# board.net
KiCad netlist of a schematic drawn in EAGLE
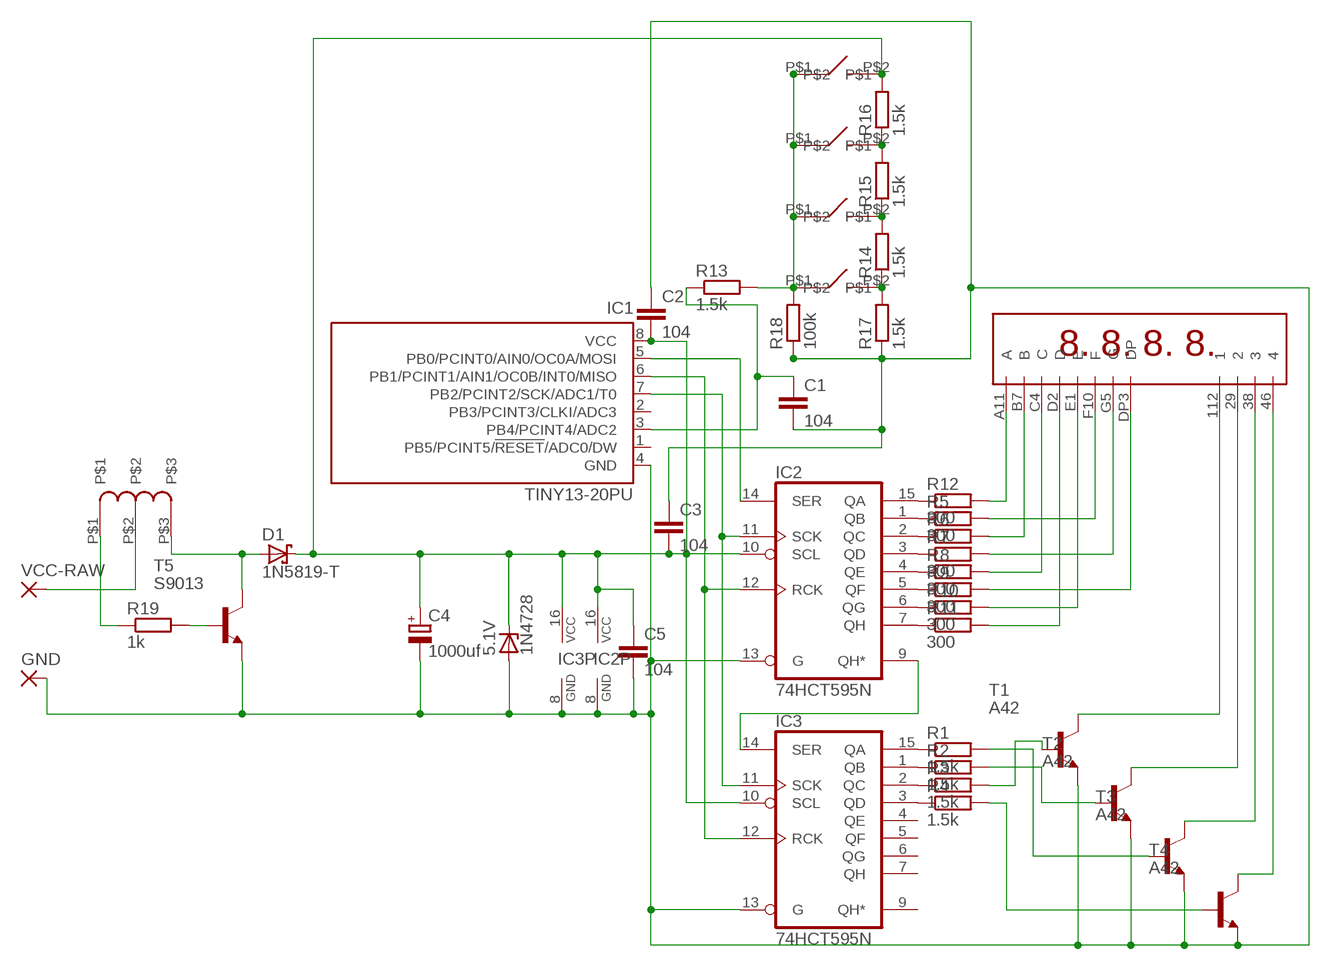
[diagram p0: schematic, sheet 1]

(export (version "E")
  (design (tool "Eeschema 10.0.6"))
  (components
    (comp (ref "5.1V")
      (value "1N4728")
      (footprint "eagle-import:DO41Z10")
      (libsource (lib "eagle-import") (part "1N4728"))
    )
    (comp (ref "BTN1")
      (value "BTN-6X6")
      (footprint "eagle-import:BTN-6X6")
      (libsource (lib "eagle-import") (part "BTN-6X6"))
    )
    (comp (ref "BTN2")
      (value "BTN-6X6")
      (footprint "eagle-import:BTN-6X6")
      (libsource (lib "eagle-import") (part "BTN-6X6"))
    )
    (comp (ref "BTN3")
      (value "BTN-6X6")
      (footprint "eagle-import:BTN-6X6")
      (libsource (lib "eagle-import") (part "BTN-6X6"))
    )
    (comp (ref "BTN4")
      (value "BTN-6X6")
      (footprint "eagle-import:BTN-6X6")
      (libsource (lib "eagle-import") (part "BTN-6X6"))
    )
    (comp (ref "C1")
      (value "104")
      (footprint "eagle-import:C050-025X075")
      (libsource (lib "eagle-import") (part "C-EU050-025X075"))
    )
    (comp (ref "C2")
      (value "104")
      (footprint "eagle-import:C050-025X075")
      (libsource (lib "eagle-import") (part "C-EU050-025X075"))
    )
    (comp (ref "C3")
      (value "104")
      (footprint "eagle-import:C050-025X075")
      (libsource (lib "eagle-import") (part "C-EU050-025X075"))
    )
    (comp (ref "C4")
      (value "1000uf")
      (footprint "eagle-import:E3,5-8")
      (libsource (lib "eagle-import") (part "CPOL-EUE3.5-8"))
    )
    (comp (ref "C5")
      (value "104")
      (footprint "eagle-import:C050-025X075")
      (libsource (lib "eagle-import") (part "C-EU050-025X075"))
    )
    (comp (ref "D1")
      (value "1N5819-T")
      (footprint "eagle-import:DO41-7.6")
      (libsource (lib "eagle-import") (part "1N5819-T"))
    )
    (comp (ref "GND")
      (value "2,54/0,8")
      (footprint "eagle-import:2,54_0,8")
      (libsource (lib "eagle-import") (part "2,54/0,8"))
    )
    (comp (ref "IC1")
      (value "TINY13-20PU")
      (footprint "eagle-import:DIL08")
      (fields (field (name "MPN") "ATTINY13-20PU"))
      (libsource (lib "eagle-import") (part "TINY13PU-20"))
    )
    (comp (ref "IC2")
      (value "74HCT595N")
      (footprint "eagle-import:DIL16")
      (libsource (lib "eagle-import") (part "74595NHCT"))
    )
    (comp (ref "IC3")
      (value "74HCT595N")
      (footprint "eagle-import:DIL16")
      (libsource (lib "eagle-import") (part "74595NHCT"))
    )
    (comp (ref "R1")
      (value "1.5k")
      (footprint "eagle-import:0207_2V")
      (libsource (lib "eagle-import") (part "resistor_348_R-EU_0207/2V"))
    )
    (comp (ref "R2")
      (value "1.5k")
      (footprint "eagle-import:0207_2V")
      (libsource (lib "eagle-import") (part "resistor_348_R-EU_0207/2V"))
    )
    (comp (ref "R3")
      (value "1.5k")
      (footprint "eagle-import:0207_2V")
      (libsource (lib "eagle-import") (part "resistor_348_R-EU_0207/2V"))
    )
    (comp (ref "R4")
      (value "1.5k")
      (footprint "eagle-import:0207_2V")
      (libsource (lib "eagle-import") (part "resistor_348_R-EU_0207/2V"))
    )
    (comp (ref "R5")
      (value "300")
      (footprint "eagle-import:0207_2V")
      (libsource (lib "eagle-import") (part "resistor_348_R-EU_0207/2V"))
    )
    (comp (ref "R6")
      (value "R-EU_0207/2V")
      (footprint "eagle-import:0207_2V")
      (libsource (lib "eagle-import") (part "resistor_348_R-EU_0207/2V"))
    )
    (comp (ref "R7")
      (value "300")
      (footprint "eagle-import:0207_2V")
      (libsource (lib "eagle-import") (part "resistor_348_R-EU_0207/2V"))
    )
    (comp (ref "R8")
      (value "300")
      (footprint "eagle-import:0207_2V")
      (libsource (lib "eagle-import") (part "resistor_348_R-EU_0207/2V"))
    )
    (comp (ref "R9")
      (value "300")
      (footprint "eagle-import:0207_2V")
      (libsource (lib "eagle-import") (part "resistor_348_R-EU_0207/2V"))
    )
    (comp (ref "R10")
      (value "300")
      (footprint "eagle-import:0207_2V")
      (libsource (lib "eagle-import") (part "resistor_348_R-EU_0207/2V"))
    )
    (comp (ref "R11")
      (value "300")
      (footprint "eagle-import:0207_2V")
      (libsource (lib "eagle-import") (part "resistor_348_R-EU_0207/2V"))
    )
    (comp (ref "R12")
      (value "300")
      (footprint "eagle-import:0207_2V")
      (libsource (lib "eagle-import") (part "resistor_348_R-EU_0207/2V"))
    )
    (comp (ref "R13")
      (value "1.5k")
      (footprint "eagle-import:0204_7")
      (libsource (lib "eagle-import") (part "resistor_348_R-EU_0204/7"))
    )
    (comp (ref "R14")
      (value "1.5k")
      (footprint "eagle-import:0204_7")
      (libsource (lib "eagle-import") (part "R-EU_0204/7"))
    )
    (comp (ref "R15")
      (value "1.5k")
      (footprint "eagle-import:0204_7")
      (libsource (lib "eagle-import") (part "R-EU_0204/7"))
    )
    (comp (ref "R16")
      (value "1.5k")
      (footprint "eagle-import:0204_7")
      (libsource (lib "eagle-import") (part "R-EU_0204/7"))
    )
    (comp (ref "R17")
      (value "1.5k")
      (footprint "eagle-import:0204_7")
      (libsource (lib "eagle-import") (part "R-EU_0204/7"))
    )
    (comp (ref "R18")
      (value "100k")
      (footprint "eagle-import:0204_7")
      (libsource (lib "eagle-import") (part "resistor_348_R-EU_0204/7"))
    )
    (comp (ref "R19")
      (value "1k")
      (footprint "eagle-import:0207_2V")
      (libsource (lib "eagle-import") (part "resistor_348_R-EU_0207/2V"))
    )
    (comp (ref "T1")
      (value "A42")
      (footprint "eagle-import:TO92-EBC")
      (libsource (lib "eagle-import") (part "-NPN-TO92-EBCMPSA42"))
    )
    (comp (ref "T2")
      (value "A42")
      (footprint "eagle-import:TO92-EBC")
      (libsource (lib "eagle-import") (part "-NPN-TO92-EBCMPSA42"))
    )
    (comp (ref "T3")
      (value "A42")
      (footprint "eagle-import:TO92-EBC")
      (libsource (lib "eagle-import") (part "-NPN-TO92-EBCMPSA42"))
    )
    (comp (ref "T4")
      (value "A42")
      (footprint "eagle-import:TO92-EBC")
      (libsource (lib "eagle-import") (part "-NPN-TO92-EBCMPSA42"))
    )
    (comp (ref "T5")
      (value "S9013")
      (footprint "eagle-import:TO92-EBC")
      (libsource (lib "eagle-import") (part "-NPN-TO92-EBCMPSA42"))
    )
    (comp (ref "U$1")
      (value "KL-5641-ASR")
      (footprint "eagle-import:KL-5641-ASR")
      (libsource (lib "eagle-import") (part "KL-5641-ASR"))
    )
    (comp (ref "U$3")
      (value "TRANS")
      (footprint "eagle-import:TRANS")
      (libsource (lib "eagle-import") (part "TRANS"))
    )
    (comp (ref "VCC-RAW")
      (value "2,54/0,8")
      (footprint "eagle-import:2,54_0,8")
      (libsource (lib "eagle-import") (part "2,54/0,8"))
    )
  )
  (nets
    (net (code "1") (name "Net-(BTN1-PadP$1)") (class "Default")
      (node (ref "BTN1") (pin "P$1") (pinfunction "P$1_P$1") (pintype "bidirectional"))
      (node (ref "BTN2") (pin "P$1") (pinfunction "P$1_P$1") (pintype "bidirectional"))
      (node (ref "BTN3") (pin "P$1") (pinfunction "P$1_P$1") (pintype "bidirectional"))
      (node (ref "BTN4") (pin "P$1") (pinfunction "P$1_P$1") (pintype "bidirectional"))
      (node (ref "R13") (pin "2") (pinfunction "2_2") (pintype "passive"))
      (node (ref "R18") (pin "2") (pinfunction "2_2") (pintype "passive"))
    )
    (net (code "2") (name "Net-(BTN2-PadP$2)") (class "Default")
      (node (ref "BTN2") (pin "P$2") (pinfunction "P$2_P$2") (pintype "bidirectional"))
      (node (ref "R15") (pin "2") (pinfunction "2_2") (pintype "passive"))
      (node (ref "R16") (pin "1") (pinfunction "1_1") (pintype "passive"))
    )
    (net (code "3") (name "Net-(BTN3-PadP$2)") (class "Default")
      (node (ref "BTN3") (pin "P$2") (pinfunction "P$2_P$2") (pintype "bidirectional"))
      (node (ref "R14") (pin "2") (pinfunction "2_2") (pintype "passive"))
      (node (ref "R15") (pin "1") (pinfunction "1_1") (pintype "passive"))
    )
    (net (code "4") (name "Net-(BTN4-PadP$2)") (class "Default")
      (node (ref "BTN4") (pin "P$2") (pinfunction "P$2_P$2") (pintype "bidirectional"))
      (node (ref "R14") (pin "1") (pinfunction "1_1") (pintype "passive"))
      (node (ref "R17") (pin "2") (pinfunction "2_2") (pintype "passive"))
    )
    (net (code "5") (name "Net-(D1-PadA)") (class "Default")
      (node (ref "D1") (pin "A") (pinfunction "A_A") (pintype "passive"))
      (node (ref "T5") (pin "C") (pinfunction "C_C") (pintype "passive"))
      (node (ref "U$3") (pin "P$3") (pinfunction "P$3_P$3") (pintype "bidirectional"))
    )
    (net (code "6") (name "Net-(GND-P)") (class "Default")
      (node (ref "5.1V") (pin "A") (pinfunction "A_A") (pintype "passive"))
      (node (ref "C1") (pin "2") (pinfunction "2_2") (pintype "passive"))
      (node (ref "C2") (pin "1") (pinfunction "1_1") (pintype "passive"))
      (node (ref "C3") (pin "1") (pinfunction "1_1") (pintype "passive"))
      (node (ref "C4") (pin "-") (pinfunction "-_-") (pintype "passive"))
      (node (ref "C5") (pin "2") (pinfunction "2_2") (pintype "passive"))
      (node (ref "GND") (pin "1") (pinfunction "P_1") (pintype "passive"))
      (node (ref "IC1") (pin "4") (pinfunction "GND_4") (pintype "power_in"))
      (node (ref "IC2") (pin "13") (pinfunction "G_13") (pintype "input"))
      (node (ref "IC2") (pin "8") (pinfunction "GND_8") (pintype "power_in"))
      (node (ref "IC3") (pin "13") (pinfunction "G_13") (pintype "input"))
      (node (ref "IC3") (pin "8") (pinfunction "GND_8") (pintype "power_in"))
      (node (ref "R17") (pin "1") (pinfunction "1_1") (pintype "passive"))
      (node (ref "R18") (pin "1") (pinfunction "1_1") (pintype "passive"))
      (node (ref "T1") (pin "E") (pinfunction "E_E") (pintype "passive"))
      (node (ref "T2") (pin "E") (pinfunction "E_E") (pintype "passive"))
      (node (ref "T3") (pin "E") (pinfunction "E_E") (pintype "passive"))
      (node (ref "T4") (pin "E") (pinfunction "E_E") (pintype "passive"))
      (node (ref "T5") (pin "E") (pinfunction "E_E") (pintype "passive"))
    )
    (net (code "7") (name "Net-(IC1-PB0{slash}PCINT0{slash}AIN0{slash}OC0A{slash}MOSI)") (class "Default")
      (node (ref "IC1") (pin "5") (pinfunction "PB0/PCINT0/AIN0/OC0A/MOSI_5") (pintype "bidirectional"))
      (node (ref "IC2") (pin "14") (pinfunction "SER_14") (pintype "input"))
    )
    (net (code "8") (name "Net-(IC1-PB1{slash}PCINT1{slash}AIN1{slash}OC0B{slash}INT0{slash}MISO)") (class "Default")
      (node (ref "IC1") (pin "6") (pinfunction "PB1/PCINT1/AIN1/OC0B/INT0/MISO_6") (pintype "bidirectional"))
      (node (ref "IC2") (pin "12") (pinfunction "RCK_12") (pintype "input"))
      (node (ref "IC3") (pin "12") (pinfunction "RCK_12") (pintype "input"))
    )
    (net (code "9") (name "Net-(IC1-PB2{slash}PCINT2{slash}SCK{slash}ADC1{slash}T0)") (class "Default")
      (node (ref "IC1") (pin "7") (pinfunction "PB2/PCINT2/SCK/ADC1/T0_7") (pintype "bidirectional"))
      (node (ref "IC2") (pin "11") (pinfunction "SCK_11") (pintype "input"))
      (node (ref "IC3") (pin "11") (pinfunction "SCK_11") (pintype "input"))
    )
    (net (code "10") (name "Net-(IC1-PB4{slash}PCINT4{slash}ADC2)") (class "Default")
      (node (ref "C1") (pin "1") (pinfunction "1_1") (pintype "passive"))
      (node (ref "IC1") (pin "3") (pinfunction "PB4/PCINT4/ADC2_3") (pintype "bidirectional"))
      (node (ref "R13") (pin "1") (pinfunction "1_1") (pintype "passive"))
    )
    (net (code "11") (name "Net-(IC1-VCC)") (class "Default")
      (node (ref "5.1V") (pin "C") (pinfunction "C_C") (pintype "passive"))
      (node (ref "BTN1") (pin "P$2") (pinfunction "P$2_P$2") (pintype "bidirectional"))
      (node (ref "C2") (pin "2") (pinfunction "2_2") (pintype "passive"))
      (node (ref "C3") (pin "2") (pinfunction "2_2") (pintype "passive"))
      (node (ref "C4") (pin "+") (pinfunction "+_+") (pintype "passive"))
      (node (ref "C5") (pin "1") (pinfunction "1_1") (pintype "passive"))
      (node (ref "D1") (pin "C") (pinfunction "C_C") (pintype "passive"))
      (node (ref "IC1") (pin "8") (pinfunction "VCC_8") (pintype "power_in"))
      (node (ref "IC2") (pin "10") (pinfunction "SCL_10") (pintype "input"))
      (node (ref "IC2") (pin "16") (pinfunction "VCC_16") (pintype "power_in"))
      (node (ref "IC3") (pin "10") (pinfunction "SCL_10") (pintype "input"))
      (node (ref "IC3") (pin "16") (pinfunction "VCC_16") (pintype "power_in"))
      (node (ref "R16") (pin "2") (pinfunction "2_2") (pintype "passive"))
    )
    (net (code "12") (name "Net-(IC2A-QA)") (class "Default")
      (node (ref "IC2") (pin "15") (pinfunction "QA_15") (pintype "tri_state"))
      (node (ref "R12") (pin "1") (pinfunction "1_1") (pintype "passive"))
    )
    (net (code "13") (name "Net-(IC2A-QB)") (class "Default")
      (node (ref "IC2") (pin "1") (pinfunction "QB_1") (pintype "tri_state"))
      (node (ref "R5") (pin "1") (pinfunction "1_1") (pintype "passive"))
    )
    (net (code "14") (name "Net-(IC2A-QC)") (class "Default")
      (node (ref "IC2") (pin "2") (pinfunction "QC_2") (pintype "tri_state"))
      (node (ref "R6") (pin "1") (pinfunction "1_1") (pintype "passive"))
    )
    (net (code "15") (name "Net-(IC2A-QD)") (class "Default")
      (node (ref "IC2") (pin "3") (pinfunction "QD_3") (pintype "tri_state"))
      (node (ref "R7") (pin "1") (pinfunction "1_1") (pintype "passive"))
    )
    (net (code "16") (name "Net-(IC2A-QE)") (class "Default")
      (node (ref "IC2") (pin "4") (pinfunction "QE_4") (pintype "tri_state"))
      (node (ref "R8") (pin "1") (pinfunction "1_1") (pintype "passive"))
    )
    (net (code "17") (name "Net-(IC2A-QF)") (class "Default")
      (node (ref "IC2") (pin "5") (pinfunction "QF_5") (pintype "tri_state"))
      (node (ref "R9") (pin "1") (pinfunction "1_1") (pintype "passive"))
    )
    (net (code "18") (name "Net-(IC2A-QG)") (class "Default")
      (node (ref "IC2") (pin "6") (pinfunction "QG_6") (pintype "tri_state"))
      (node (ref "R10") (pin "1") (pinfunction "1_1") (pintype "passive"))
    )
    (net (code "19") (name "Net-(IC2A-QH)") (class "Default")
      (node (ref "IC2") (pin "7") (pinfunction "QH_7") (pintype "tri_state"))
      (node (ref "R11") (pin "1") (pinfunction "1_1") (pintype "passive"))
    )
    (net (code "20") (name "Net-(IC2A-QH*)") (class "Default")
      (node (ref "IC2") (pin "9") (pinfunction "QH*_9") (pintype "tri_state"))
      (node (ref "IC3") (pin "14") (pinfunction "SER_14") (pintype "input"))
    )
    (net (code "21") (name "Net-(IC3A-QA)") (class "Default")
      (node (ref "IC3") (pin "15") (pinfunction "QA_15") (pintype "tri_state"))
      (node (ref "R1") (pin "1") (pinfunction "1_1") (pintype "passive"))
    )
    (net (code "22") (name "Net-(IC3A-QB)") (class "Default")
      (node (ref "IC3") (pin "1") (pinfunction "QB_1") (pintype "tri_state"))
      (node (ref "R2") (pin "1") (pinfunction "1_1") (pintype "passive"))
    )
    (net (code "23") (name "Net-(IC3A-QC)") (class "Default")
      (node (ref "IC3") (pin "2") (pinfunction "QC_2") (pintype "tri_state"))
      (node (ref "R3") (pin "1") (pinfunction "1_1") (pintype "passive"))
    )
    (net (code "24") (name "Net-(IC3A-QD)") (class "Default")
      (node (ref "IC3") (pin "3") (pinfunction "QD_3") (pintype "tri_state"))
      (node (ref "R4") (pin "1") (pinfunction "1_1") (pintype "passive"))
    )
    (net (code "25") (name "Net-(R1-Pad2)") (class "Default")
      (node (ref "R1") (pin "2") (pinfunction "2_2") (pintype "passive"))
      (node (ref "T3") (pin "B") (pinfunction "B_B") (pintype "passive"))
    )
    (net (code "26") (name "Net-(R2-Pad2)") (class "Default")
      (node (ref "R2") (pin "2") (pinfunction "2_2") (pintype "passive"))
      (node (ref "T2") (pin "B") (pinfunction "B_B") (pintype "passive"))
    )
    (net (code "27") (name "Net-(R3-Pad2)") (class "Default")
      (node (ref "R3") (pin "2") (pinfunction "2_2") (pintype "passive"))
      (node (ref "T1") (pin "B") (pinfunction "B_B") (pintype "passive"))
    )
    (net (code "28") (name "Net-(R4-Pad2)") (class "Default")
      (node (ref "R4") (pin "2") (pinfunction "2_2") (pintype "passive"))
      (node (ref "T4") (pin "B") (pinfunction "B_B") (pintype "passive"))
    )
    (net (code "29") (name "Net-(R19-Pad1)") (class "Default")
      (node (ref "R19") (pin "1") (pinfunction "1_1") (pintype "passive"))
      (node (ref "U$3") (pin "P$1") (pinfunction "P$1_P$1") (pintype "bidirectional"))
    )
    (net (code "30") (name "Net-(R19-Pad2)") (class "Default")
      (node (ref "R19") (pin "2") (pinfunction "2_2") (pintype "passive"))
      (node (ref "T5") (pin "B") (pinfunction "B_B") (pintype "passive"))
    )
    (net (code "31") (name "Net-(U$1-1)") (class "Default")
      (node (ref "T1") (pin "C") (pinfunction "C_C") (pintype "passive"))
      (node (ref "U$1") (pin "112") (pinfunction "1_112") (pintype "bidirectional"))
    )
    (net (code "32") (name "Net-(U$1-2)") (class "Default")
      (node (ref "T2") (pin "C") (pinfunction "C_C") (pintype "passive"))
      (node (ref "U$1") (pin "29") (pinfunction "2_29") (pintype "bidirectional"))
    )
    (net (code "33") (name "Net-(U$1-3)") (class "Default")
      (node (ref "T3") (pin "C") (pinfunction "C_C") (pintype "passive"))
      (node (ref "U$1") (pin "38") (pinfunction "3_38") (pintype "bidirectional"))
    )
    (net (code "34") (name "Net-(U$1-4)") (class "Default")
      (node (ref "T4") (pin "C") (pinfunction "C_C") (pintype "passive"))
      (node (ref "U$1") (pin "46") (pinfunction "4_46") (pintype "bidirectional"))
    )
    (net (code "35") (name "Net-(U$1-A)") (class "Default")
      (node (ref "R12") (pin "2") (pinfunction "2_2") (pintype "passive"))
      (node (ref "U$1") (pin "A11") (pinfunction "A_A11") (pintype "bidirectional"))
    )
    (net (code "36") (name "Net-(U$1-B)") (class "Default")
      (node (ref "R6") (pin "2") (pinfunction "2_2") (pintype "passive"))
      (node (ref "U$1") (pin "B7") (pinfunction "B_B7") (pintype "bidirectional"))
    )
    (net (code "37") (name "Net-(U$1-C)") (class "Default")
      (node (ref "R8") (pin "2") (pinfunction "2_2") (pintype "passive"))
      (node (ref "U$1") (pin "C4") (pinfunction "C_C4") (pintype "bidirectional"))
    )
    (net (code "38") (name "Net-(U$1-D)") (class "Default")
      (node (ref "R11") (pin "2") (pinfunction "2_2") (pintype "passive"))
      (node (ref "U$1") (pin "D2") (pinfunction "D_D2") (pintype "bidirectional"))
    )
    (net (code "39") (name "Net-(U$1-DP)") (class "Default")
      (node (ref "R9") (pin "2") (pinfunction "2_2") (pintype "passive"))
      (node (ref "U$1") (pin "DP3") (pinfunction "DP_DP3") (pintype "bidirectional"))
    )
    (net (code "40") (name "Net-(U$1-E)") (class "Default")
      (node (ref "R10") (pin "2") (pinfunction "2_2") (pintype "passive"))
      (node (ref "U$1") (pin "E1") (pinfunction "E_E1") (pintype "bidirectional"))
    )
    (net (code "41") (name "Net-(U$1-F)") (class "Default")
      (node (ref "R5") (pin "2") (pinfunction "2_2") (pintype "passive"))
      (node (ref "U$1") (pin "F10") (pinfunction "F_F10") (pintype "bidirectional"))
    )
    (net (code "42") (name "Net-(U$1-G)") (class "Default")
      (node (ref "R7") (pin "2") (pinfunction "2_2") (pintype "passive"))
      (node (ref "U$1") (pin "G5") (pinfunction "G_G5") (pintype "bidirectional"))
    )
    (net (code "43") (name "Net-(VCC-RAW-P)") (class "Default")
      (node (ref "U$3") (pin "P$2") (pinfunction "P$2_P$2") (pintype "bidirectional"))
      (node (ref "VCC-RAW") (pin "1") (pinfunction "P_1") (pintype "passive"))
    )
    (net (code "44") (name "unconnected-(IC1-PB3{slash}PCINT3{slash}CLKI{slash}ADC3-Pad2)") (class "Default")
      (node (ref "IC1") (pin "2") (pinfunction "PB3/PCINT3/CLKI/ADC3_2") (pintype "bidirectional"))
    )
    (net (code "45") (name "unconnected-(IC1-PB5{slash}PCINT5{slash}~{RESET}{slash}ADC0{slash}DW-Pad1)") (class "Default")
      (node (ref "IC1") (pin "1") (pinfunction "PB5/PCINT5/~{RESET}/ADC0/DW_1") (pintype "bidirectional"))
    )
    (net (code "46") (name "unconnected-(IC3A-QE-Pad4)") (class "Default")
      (node (ref "IC3") (pin "4") (pinfunction "QE_4") (pintype "tri_state"))
    )
    (net (code "47") (name "unconnected-(IC3A-QF-Pad5)") (class "Default")
      (node (ref "IC3") (pin "5") (pinfunction "QF_5") (pintype "tri_state"))
    )
    (net (code "48") (name "unconnected-(IC3A-QG-Pad6)") (class "Default")
      (node (ref "IC3") (pin "6") (pinfunction "QG_6") (pintype "tri_state"))
    )
    (net (code "49") (name "unconnected-(IC3A-QH*-Pad9)") (class "Default")
      (node (ref "IC3") (pin "9") (pinfunction "QH*_9") (pintype "tri_state"))
    )
    (net (code "50") (name "unconnected-(IC3A-QH-Pad7)") (class "Default")
      (node (ref "IC3") (pin "7") (pinfunction "QH_7") (pintype "tri_state"))
    )
  )
)
